# percepcao_externa_official.net
KiCad netlist of a schematic drawn in Altium Designer
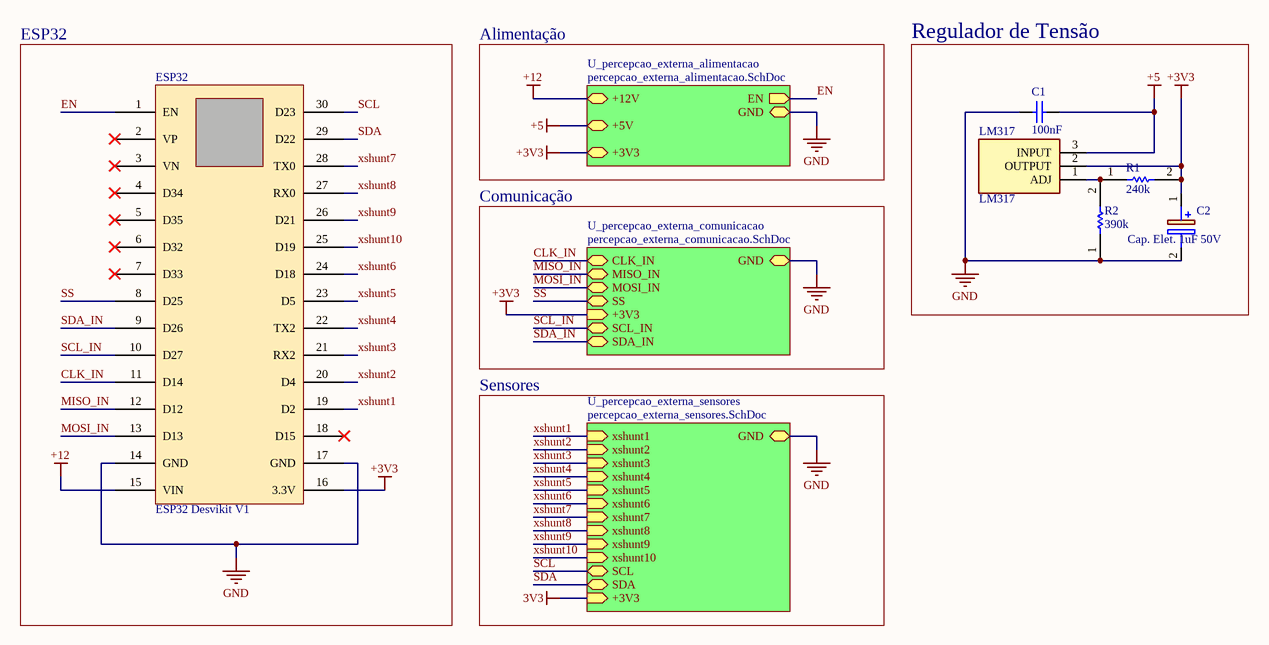
[diagram p0: percepcao_externa_official.SchDoc]

(export (version "E")
  (design (tool "Eeschema 10.0.6"))
  (components
    (comp (ref "C1")
      (value "100nF")
      (footprint "CAP CER DISK 10uF 50V")
      (description "CAP CER DISK 10uF 50V")
      (fields (field (name "MANUFACTURER PART NUMBER") "IMP14925"))
      (libsource (lib "RoboHospitalar") (part "CAP CER DISK 10uF 50V_1"))
    )
    (comp (ref "C2")
      (value "Cap. Elet. 1uF 50V")
      (footprint "Cap. Elet. 470uF 16V")
      (description "Aluminum Organic Polymer Capacitors 16volts 470uF ESR 10mohm")
      (fields
        (field (name "MANUFACTURER_PART_NUMBER") "16SEPC470M")
        (field (name "MOUSER PART NUMBER") "667-16SEPC470M")
      )
      (libsource (lib "esp32") (part "Cap. Elet. 470 uF 16V"))
    )
    (comp (ref "ESP32")
      (value "ESP32 Desvikit V1")
      (footprint "ESP32_Desvikit_v1")
      (description "microcontrolador com moculo bluethoth e wifi")
      (fields (field (name "Comment") "microcontrolador"))
      (libsource (lib "Sinaliza玢o_Official") (part "ESP32 Desvikit v1"))
    )
    (comp (ref "LM317")
      (value "LM317")
      (footprint "SamacSys:TO254P467X1016X1971-3P")
      (description "Integrated Circuit")
      (libsource (lib "RoboHospitalar") (part "LM317"))
    )
    (comp (ref "R1")
      (value "240k")
      (footprint "RESC3216X60N")
      (description "RES 1206 5%")
      (fields
        (field (name "MANUFACTURER_PART_NUMBER") "CRCW12064K70FKEA")
        (field (name "MOUSER PART NUMBER") "71-CRCW1206-4.7K-E3")
      )
      (libsource (lib "RoboHospitalar") (part "RES 1206"))
    )
    (comp (ref "R2")
      (value "390k")
      (footprint "RESC3216X60N")
      (description "RES 1206 5%")
      (fields
        (field (name "MANUFACTURER_PART_NUMBER") "CRCW12064K70FKEA")
        (field (name "MOUSER PART NUMBER") "71-CRCW1206-4.7K-E3")
      )
      (libsource (lib "RoboHospitalar") (part "RES 1206"))
    )
  )
  (nets
    (net (code "1") (name "+3V3") (class "Default")
      (node (ref "C2") (pin "1") (pinfunction "+_1") (pintype "passive"))
      (node (ref "ESP32") (pin "16") (pinfunction "3.3V_16") (pintype "passive"))
      (node (ref "LM317") (pin "2") (pinfunction "OUTPUT_2") (pintype "passive"))
      (node (ref "R1") (pin "2") (pinfunction "2_2") (pintype "passive"))
    )
    (net (code "2") (name "+5") (class "Default")
      (node (ref "C1") (pin "2") (pinfunction "2_2") (pintype "passive"))
      (node (ref "LM317") (pin "3") (pinfunction "INPUT_3") (pintype "passive"))
    )
    (net (code "3") (name "+12") (class "Default")
      (node (ref "ESP32") (pin "15") (pinfunction "VIN_15") (pintype "passive"))
    )
    (net (code "4") (name "/CLK_IN") (class "Default")
      (node (ref "ESP32") (pin "11") (pinfunction "D14_11") (pintype "passive"))
    )
    (net (code "5") (name "/EN") (class "Default")
      (node (ref "ESP32") (pin "1") (pinfunction "EN_1") (pintype "passive"))
    )
    (net (code "6") (name "/MISO_IN") (class "Default")
      (node (ref "ESP32") (pin "12") (pinfunction "D12_12") (pintype "passive"))
    )
    (net (code "7") (name "/MOSI_IN") (class "Default")
      (node (ref "ESP32") (pin "13") (pinfunction "D13_13") (pintype "passive"))
    )
    (net (code "8") (name "/SCL") (class "Default")
      (node (ref "ESP32") (pin "30") (pinfunction "D23_30") (pintype "passive"))
    )
    (net (code "9") (name "/SCL_IN") (class "Default")
      (node (ref "ESP32") (pin "10") (pinfunction "D27_10") (pintype "passive"))
    )
    (net (code "10") (name "/SDA") (class "Default")
      (node (ref "ESP32") (pin "29") (pinfunction "D22_29") (pintype "passive"))
    )
    (net (code "11") (name "/SDA_IN") (class "Default")
      (node (ref "ESP32") (pin "9") (pinfunction "D26_9") (pintype "passive"))
    )
    (net (code "12") (name "/SS") (class "Default")
      (node (ref "ESP32") (pin "8") (pinfunction "D25_8") (pintype "passive"))
    )
    (net (code "13") (name "/xshunt1") (class "Default")
      (node (ref "ESP32") (pin "19") (pinfunction "D2_19") (pintype "passive"))
    )
    (net (code "14") (name "/xshunt2") (class "Default")
      (node (ref "ESP32") (pin "20") (pinfunction "D4_20") (pintype "passive"))
    )
    (net (code "15") (name "/xshunt3") (class "Default")
      (node (ref "ESP32") (pin "21") (pinfunction "RX2_21") (pintype "passive"))
    )
    (net (code "16") (name "/xshunt4") (class "Default")
      (node (ref "ESP32") (pin "22") (pinfunction "TX2_22") (pintype "passive"))
    )
    (net (code "17") (name "/xshunt5") (class "Default")
      (node (ref "ESP32") (pin "23") (pinfunction "D5_23") (pintype "passive"))
    )
    (net (code "18") (name "/xshunt6") (class "Default")
      (node (ref "ESP32") (pin "24") (pinfunction "D18_24") (pintype "passive"))
    )
    (net (code "19") (name "/xshunt7") (class "Default")
      (node (ref "ESP32") (pin "28") (pinfunction "TX0_28") (pintype "passive"))
    )
    (net (code "20") (name "/xshunt8") (class "Default")
      (node (ref "ESP32") (pin "27") (pinfunction "RX0_27") (pintype "passive"))
    )
    (net (code "21") (name "/xshunt9") (class "Default")
      (node (ref "ESP32") (pin "26") (pinfunction "D21_26") (pintype "passive"))
    )
    (net (code "22") (name "/xshunt10") (class "Default")
      (node (ref "ESP32") (pin "25") (pinfunction "D19_25") (pintype "passive"))
    )
    (net (code "24") (name "GND") (class "Default")
      (node (ref "C1") (pin "1") (pinfunction "1_1") (pintype "passive"))
      (node (ref "C2") (pin "2") (pinfunction "-_2") (pintype "passive"))
      (node (ref "ESP32") (pin "14") (pinfunction "GND_14") (pintype "passive"))
      (node (ref "ESP32") (pin "17") (pinfunction "GND_17") (pintype "passive"))
      (node (ref "R2") (pin "1") (pinfunction "1_1") (pintype "passive"))
    )
    (net (code "25") (name "Net-(LM317-ADJ)") (class "Default")
      (node (ref "LM317") (pin "1") (pinfunction "ADJ_1") (pintype "passive"))
      (node (ref "R1") (pin "1") (pinfunction "1_1") (pintype "passive"))
      (node (ref "R2") (pin "2") (pinfunction "2_2") (pintype "passive"))
    )
    (net (code "26") (name "unconnected-(ESP32-D15-Pad18)") (class "Default")
      (node (ref "ESP32") (pin "18") (pinfunction "D15_18") (pintype "passive+no_connect"))
    )
    (net (code "27") (name "unconnected-(ESP32-D32-Pad6)") (class "Default")
      (node (ref "ESP32") (pin "6") (pinfunction "D32_6") (pintype "passive+no_connect"))
    )
    (net (code "28") (name "unconnected-(ESP32-D33-Pad7)") (class "Default")
      (node (ref "ESP32") (pin "7") (pinfunction "D33_7") (pintype "passive+no_connect"))
    )
    (net (code "29") (name "unconnected-(ESP32-D34-Pad4)") (class "Default")
      (node (ref "ESP32") (pin "4") (pinfunction "D34_4") (pintype "passive+no_connect"))
    )
    (net (code "30") (name "unconnected-(ESP32-D35-Pad5)") (class "Default")
      (node (ref "ESP32") (pin "5") (pinfunction "D35_5") (pintype "passive+no_connect"))
    )
    (net (code "31") (name "unconnected-(ESP32-VN-Pad3)") (class "Default")
      (node (ref "ESP32") (pin "3") (pinfunction "VN_3") (pintype "passive+no_connect"))
    )
    (net (code "32") (name "unconnected-(ESP32-VP-Pad2)") (class "Default")
      (node (ref "ESP32") (pin "2") (pinfunction "VP_2") (pintype "passive+no_connect"))
    )
  )
)
